# InterfaceConfiguracao.net
KiCad netlist of a schematic drawn in Altium Designer
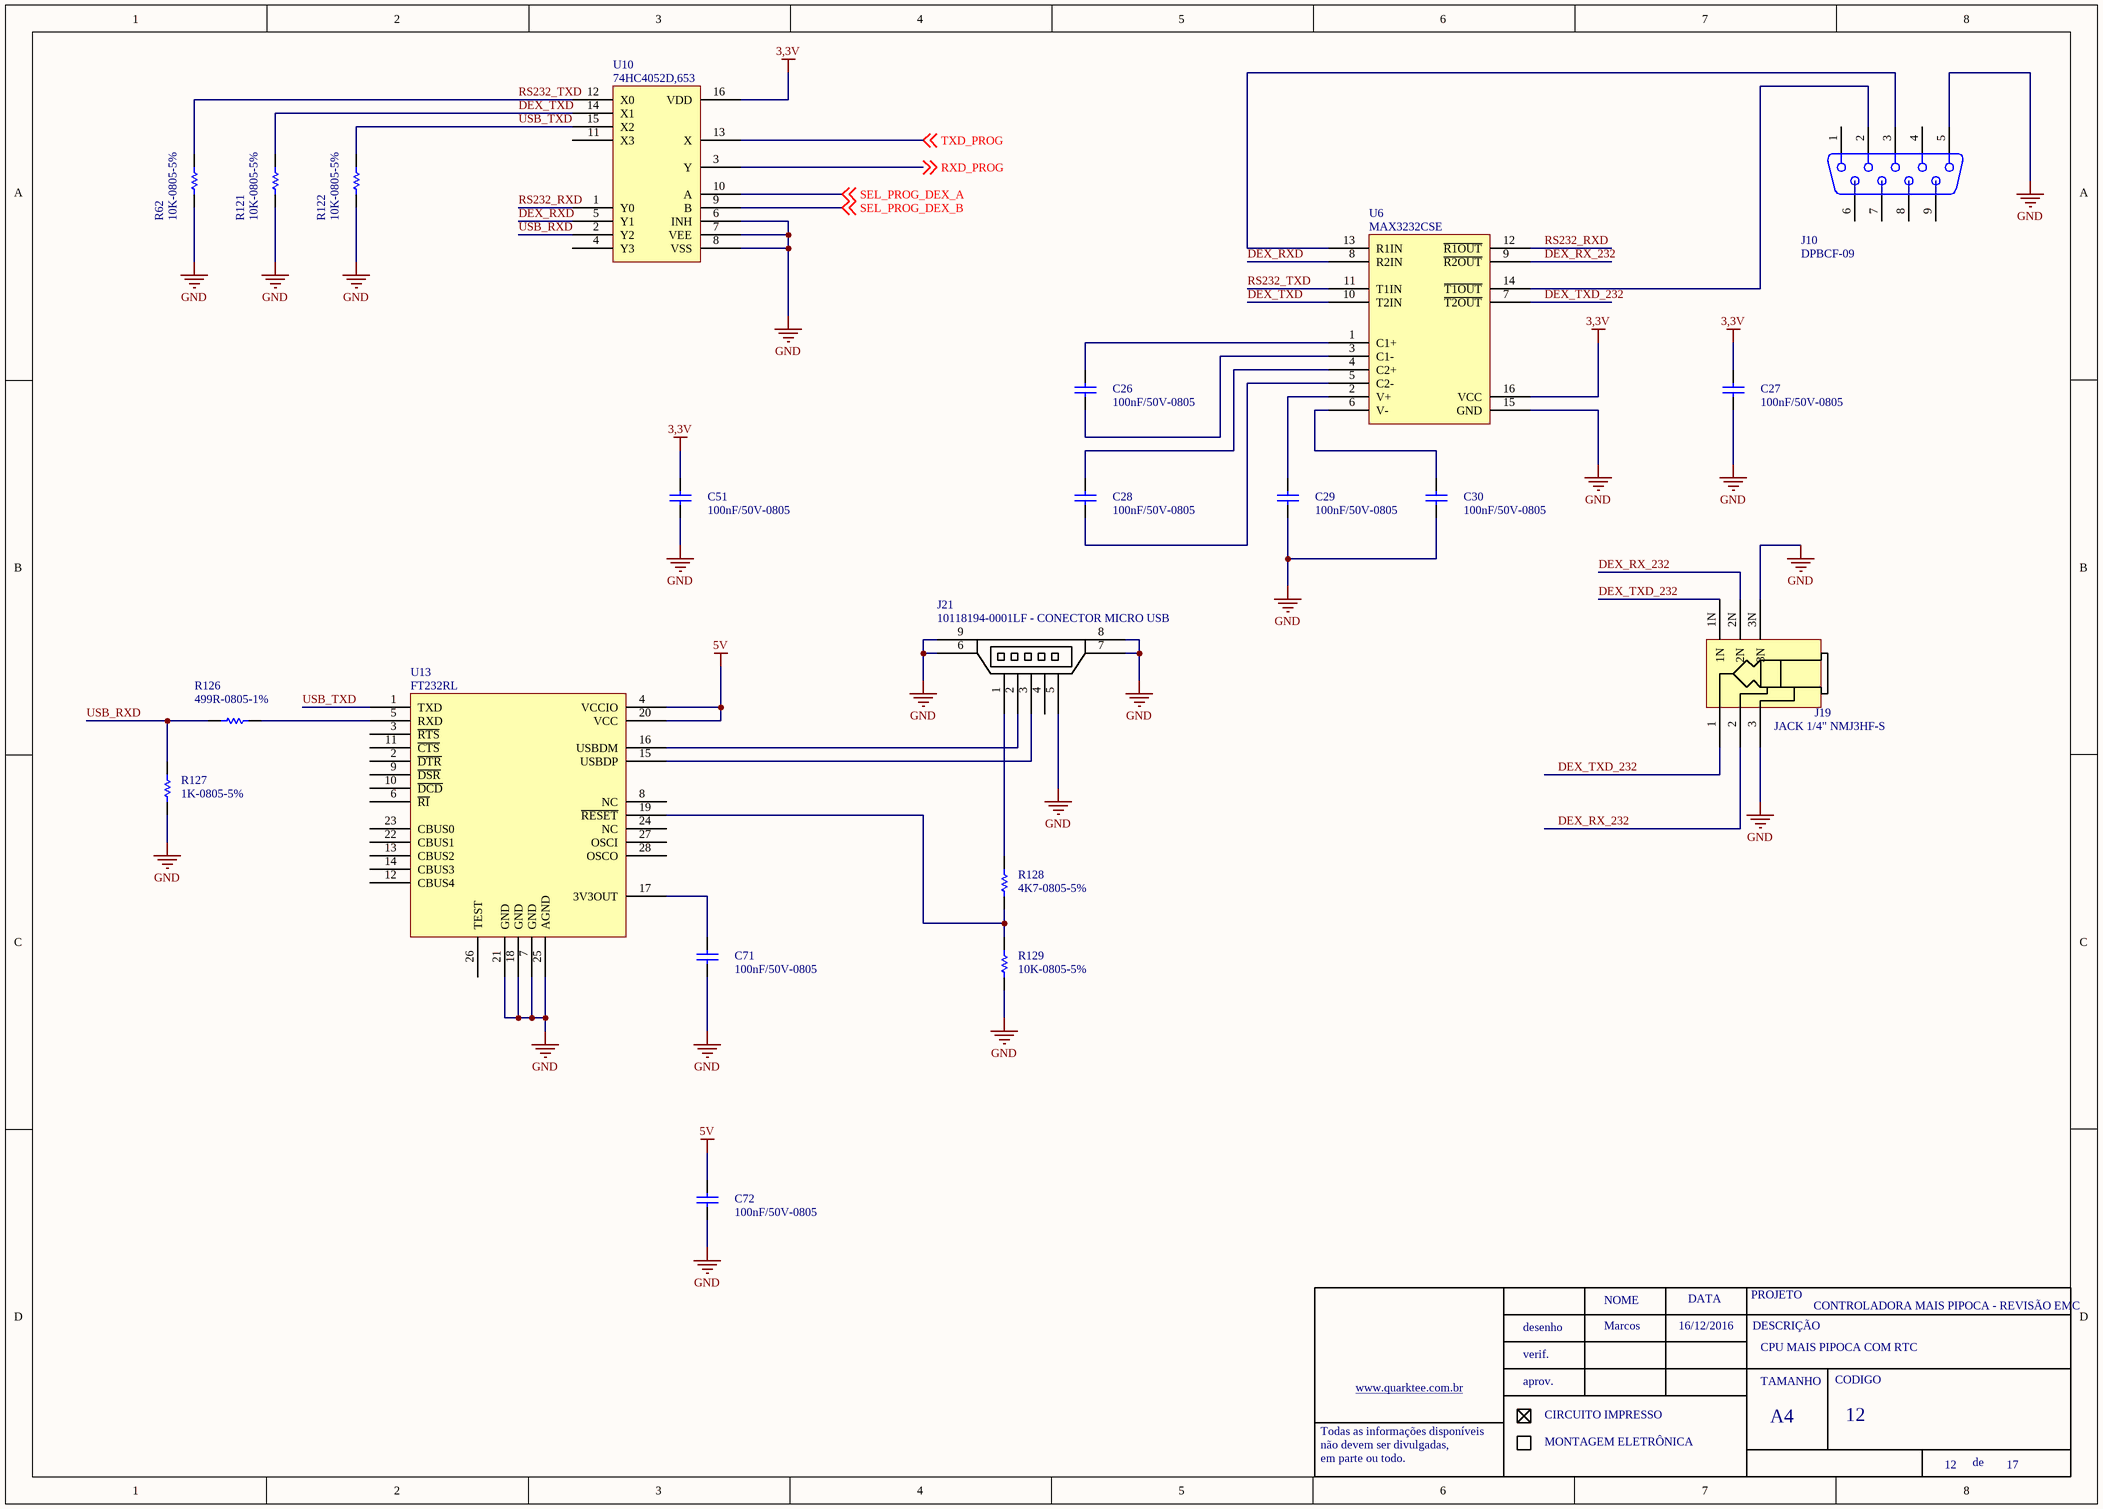
[diagram p0: InterfaceConfiguracao.SchDoc]

(export (version "E")
  (design (tool "Eeschema 10.0.6"))
  (components
    (comp (ref "C26")
      (value "100nF/50V-0805")
      (footprint "0805-REVISADO ONDA")
      (description "100nF/50-0805-NPO")
      (libsource (lib "AquinoLib") (part "100nF/50-0805-NPO"))
    )
    (comp (ref "C27")
      (value "100nF/50V-0805")
      (footprint "0805-REVISADO ONDA")
      (description "100nF/50-0805-NPO")
      (libsource (lib "AquinoLib") (part "100nF/50-0805-NPO"))
    )
    (comp (ref "C28")
      (value "100nF/50V-0805")
      (footprint "0805-REVISADO ONDA")
      (description "100nF/50-0805-NPO")
      (libsource (lib "AquinoLib") (part "100nF/50-0805-NPO"))
    )
    (comp (ref "C29")
      (value "100nF/50V-0805")
      (footprint "0805-REVISADO ONDA")
      (description "100nF/50-0805-NPO")
      (libsource (lib "AquinoLib") (part "100nF/50-0805-NPO"))
    )
    (comp (ref "C30")
      (value "100nF/50V-0805")
      (footprint "0805-REVISADO ONDA")
      (description "100nF/50-0805-NPO")
      (libsource (lib "AquinoLib") (part "100nF/50-0805-NPO"))
    )
    (comp (ref "C51")
      (value "100nF/50V-0805")
      (footprint "0805-REVISADO ONDA")
      (libsource (lib "AquinoLib") (part "100nF/50-0805-NPO"))
    )
    (comp (ref "C71")
      (value "100nF/50V-0805")
      (footprint "0805-REVISADO ONDA")
      (libsource (lib "AquinoLib") (part "100nF/50-0805-NPO"))
    )
    (comp (ref "C72")
      (value "100nF/50V-0805")
      (footprint "0805-REVISADO ONDA")
      (libsource (lib "AquinoLib") (part "100nF/50-0805-NPO"))
    )
    (comp (ref "J10")
      (value "DPBCF-09")
      (footprint "DB9-FÊMEA MONTAGEM EM PCI 180")
      (description "DBPCF-09")
      (libsource (lib "ChaveDigital3") (part "DB-9 - FÊMEA 180º MONTAGEM EM PCI"))
    )
    (comp (ref "J19")
      (value "JACK 1/4\" NMJ3HF-S")
      (description "NMJ3HF-S")
      (libsource (lib "AquinoLib") (part "NMJ3HF-S"))
    )
    (comp (ref "J21")
      (value "10118194-0001LF - CONECTOR MICRO USB")
      (libsource (lib "AquinoLib") (part "MINI_USB"))
    )
    (comp (ref "R62")
      (value "10K-0805-5%")
      (footprint "0805-REVISADO ONDA")
      (libsource (lib "AquinoLib") (part "10K-0805-5%"))
    )
    (comp (ref "R121")
      (value "10K-0805-5%")
      (footprint "0805-REVISADO ONDA")
      (libsource (lib "AquinoLib") (part "10K-0805-5%"))
    )
    (comp (ref "R122")
      (value "10K-0805-5%")
      (footprint "0805-REVISADO ONDA")
      (libsource (lib "AquinoLib") (part "10K-0805-5%"))
    )
    (comp (ref "R126")
      (value "499R-0805-1%")
      (footprint "0805-REVISADO ONDA")
      (description "1K-0805-5%")
      (libsource (lib "AquinoLib") (part "1K-0805-5%"))
    )
    (comp (ref "R127")
      (value "1K-0805-5%")
      (footprint "0805-REVISADO ONDA")
      (libsource (lib "AquinoLib") (part "1K-0805-5%"))
    )
    (comp (ref "R128")
      (value "4K7-0805-5%")
      (footprint "0805-REVISADO ONDA")
      (description "10K-0805-5%")
      (libsource (lib "AquinoLib") (part "10K-0805-5%"))
    )
    (comp (ref "R129")
      (value "10K-0805-5%")
      (footprint "0805-REVISADO ONDA")
      (libsource (lib "AquinoLib") (part "10K-0805-5%"))
    )
    (comp (ref "U6")
      (value "MAX3232CSE")
      (footprint "SOIC 16 PINOS")
      (libsource (lib "ChaveDigital3") (part "MAX3232CSE"))
    )
    (comp (ref "U10") (value "74HC4052D,653") (libsource (lib "AquinoLib") (part "CD74HC4052PWR")))
    (comp (ref "U13") (value "FT232RL") (libsource (lib "AquinoLib") (part "FT232RL")))
  )
  (nets
    (net (code "1") (name "/DEX_RXD") (class "Default")
      (node (ref "U10") (pin "5") (pinfunction "Y1_5") (pintype "passive"))
      (node (ref "U6") (pin "8") (pinfunction "R2IN_8") (pintype "passive"))
    )
    (net (code "2") (name "/DEX_RX_232") (class "Default")
      (node (ref "J19") (pin "2") (pinfunction "2_2") (pintype "passive"))
      (node (ref "J19") (pin "2N") (pinfunction "2N_2N") (pintype "passive"))
      (node (ref "U6") (pin "9") (pinfunction "~{R2OUT}_9") (pintype "passive"))
    )
    (net (code "3") (name "/DEX_TXD") (class "Default")
      (node (ref "R121") (pin "2") (pinfunction "2_2") (pintype "passive"))
      (node (ref "U10") (pin "14") (pinfunction "X1_14") (pintype "passive"))
      (node (ref "U6") (pin "10") (pinfunction "T2IN_10") (pintype "passive"))
    )
    (net (code "4") (name "/DEX_TXD_232") (class "Default")
      (node (ref "J19") (pin "1") (pinfunction "1_1") (pintype "passive"))
      (node (ref "J19") (pin "1N") (pinfunction "1N_1N") (pintype "passive"))
      (node (ref "U6") (pin "7") (pinfunction "~{T2OUT}_7") (pintype "passive"))
    )
    (net (code "5") (name "/RS232_RXD") (class "Default")
      (node (ref "U10") (pin "1") (pinfunction "Y0_1") (pintype "passive"))
      (node (ref "U6") (pin "12") (pinfunction "~{R1OUT}_12") (pintype "passive"))
    )
    (net (code "6") (name "/RS232_TXD") (class "Default")
      (node (ref "R62") (pin "2") (pinfunction "2_2") (pintype "passive"))
      (node (ref "U10") (pin "12") (pinfunction "X0_12") (pintype "passive"))
      (node (ref "U6") (pin "11") (pinfunction "T1IN_11") (pintype "passive"))
    )
    (net (code "7") (name "/USB_RXD") (class "Default")
      (node (ref "R126") (pin "1") (pinfunction "1_1") (pintype "passive"))
      (node (ref "R127") (pin "2") (pinfunction "2_2") (pintype "passive"))
      (node (ref "U10") (pin "2") (pinfunction "Y2_2") (pintype "passive"))
    )
    (net (code "8") (name "/USB_TXD") (class "Default")
      (node (ref "R122") (pin "2") (pinfunction "2_2") (pintype "passive"))
      (node (ref "U10") (pin "15") (pinfunction "X2_15") (pintype "passive"))
      (node (ref "U13") (pin "1") (pinfunction "TXD_1") (pintype "passive"))
    )
    (net (code "9") (name "3,3V") (class "Default")
      (node (ref "C27") (pin "2") (pinfunction "2_2") (pintype "passive"))
      (node (ref "C51") (pin "2") (pinfunction "2_2") (pintype "passive"))
      (node (ref "U10") (pin "16") (pinfunction "VDD_16") (pintype "passive"))
      (node (ref "U6") (pin "16") (pinfunction "VCC_16") (pintype "passive"))
    )
    (net (code "10") (name "5V") (class "Default")
      (node (ref "C72") (pin "2") (pinfunction "2_2") (pintype "passive"))
      (node (ref "U13") (pin "20") (pinfunction "VCC_20") (pintype "passive"))
      (node (ref "U13") (pin "4") (pinfunction "VCCIO_4") (pintype "passive"))
    )
    (net (code "11") (name "GND") (class "Default")
      (node (ref "C27") (pin "1") (pinfunction "1_1") (pintype "passive"))
      (node (ref "C29") (pin "1") (pinfunction "1_1") (pintype "passive"))
      (node (ref "C30") (pin "1") (pinfunction "1_1") (pintype "passive"))
      (node (ref "C51") (pin "1") (pinfunction "1_1") (pintype "passive"))
      (node (ref "C71") (pin "1") (pinfunction "1_1") (pintype "passive"))
      (node (ref "C72") (pin "1") (pinfunction "1_1") (pintype "passive"))
      (node (ref "J10") (pin "5") (pinfunction "5_5") (pintype "passive"))
      (node (ref "J19") (pin "3") (pinfunction "3_3") (pintype "passive"))
      (node (ref "J19") (pin "3N") (pinfunction "3N_3N") (pintype "passive"))
      (node (ref "J21") (pin "5") (pinfunction "5_5") (pintype "passive"))
      (node (ref "J21") (pin "6") (pinfunction "6_6") (pintype "passive"))
      (node (ref "J21") (pin "7") (pinfunction "7_7") (pintype "passive"))
      (node (ref "J21") (pin "8") (pinfunction "8_8") (pintype "passive"))
      (node (ref "J21") (pin "9") (pinfunction "9_9") (pintype "passive"))
      (node (ref "R121") (pin "1") (pinfunction "1_1") (pintype "passive"))
      (node (ref "R122") (pin "1") (pinfunction "1_1") (pintype "passive"))
      (node (ref "R127") (pin "1") (pinfunction "1_1") (pintype "passive"))
      (node (ref "R129") (pin "1") (pinfunction "1_1") (pintype "passive"))
      (node (ref "R62") (pin "1") (pinfunction "1_1") (pintype "passive"))
      (node (ref "U10") (pin "6") (pinfunction "INH_6") (pintype "passive"))
      (node (ref "U10") (pin "7") (pinfunction "VEE_7") (pintype "passive"))
      (node (ref "U10") (pin "8") (pinfunction "VSS_8") (pintype "passive"))
      (node (ref "U13") (pin "18") (pinfunction "GND_18") (pintype "passive"))
      (node (ref "U13") (pin "21") (pinfunction "GND_21") (pintype "passive"))
      (node (ref "U13") (pin "25") (pinfunction "AGND_25") (pintype "passive"))
      (node (ref "U13") (pin "7") (pinfunction "GND_7") (pintype "passive"))
      (node (ref "U6") (pin "15") (pinfunction "GND_15") (pintype "passive"))
    )
    (net (code "12") (name "Net-(J21-Pad1)") (class "Default")
      (node (ref "J21") (pin "1") (pinfunction "1_1") (pintype "passive"))
      (node (ref "R128") (pin "2") (pinfunction "2_2") (pintype "passive"))
    )
    (net (code "13") (name "Net-(U6-C1+)") (class "Default")
      (node (ref "C26") (pin "2") (pinfunction "2_2") (pintype "passive"))
      (node (ref "U6") (pin "1") (pinfunction "C1+_1") (pintype "passive"))
    )
    (net (code "14") (name "Net-(U6-C1-)") (class "Default")
      (node (ref "C26") (pin "1") (pinfunction "1_1") (pintype "passive"))
      (node (ref "U6") (pin "3") (pinfunction "C1-_3") (pintype "passive"))
    )
    (net (code "15") (name "Net-(U6-C2+)") (class "Default")
      (node (ref "C28") (pin "2") (pinfunction "2_2") (pintype "passive"))
      (node (ref "U6") (pin "4") (pinfunction "C2+_4") (pintype "passive"))
    )
    (net (code "16") (name "Net-(U6-C2-)") (class "Default")
      (node (ref "C28") (pin "1") (pinfunction "1_1") (pintype "passive"))
      (node (ref "U6") (pin "5") (pinfunction "C2-_5") (pintype "passive"))
    )
    (net (code "17") (name "Net-(U6-R1IN)") (class "Default")
      (node (ref "J10") (pin "3") (pinfunction "3_3") (pintype "passive"))
      (node (ref "U6") (pin "13") (pinfunction "R1IN_13") (pintype "passive"))
    )
    (net (code "18") (name "Net-(U6-V+)") (class "Default")
      (node (ref "C29") (pin "2") (pinfunction "2_2") (pintype "passive"))
      (node (ref "U6") (pin "2") (pinfunction "V+_2") (pintype "passive"))
    )
    (net (code "19") (name "Net-(U6-V-)") (class "Default")
      (node (ref "C30") (pin "2") (pinfunction "2_2") (pintype "passive"))
      (node (ref "U6") (pin "6") (pinfunction "V-_6") (pintype "passive"))
    )
    (net (code "20") (name "Net-(U6-~{T1OUT})") (class "Default")
      (node (ref "J10") (pin "2") (pinfunction "2_2") (pintype "passive"))
      (node (ref "U6") (pin "14") (pinfunction "~{T1OUT}_14") (pintype "passive"))
    )
    (net (code "21") (name "Net-(U13-3V3OUT)") (class "Default")
      (node (ref "C71") (pin "2") (pinfunction "2_2") (pintype "passive"))
      (node (ref "U13") (pin "17") (pinfunction "3V3OUT_17") (pintype "passive"))
    )
    (net (code "22") (name "Net-(U13-RXD)") (class "Default")
      (node (ref "R126") (pin "2") (pinfunction "2_2") (pintype "passive"))
      (node (ref "U13") (pin "5") (pinfunction "RXD_5") (pintype "passive"))
    )
    (net (code "23") (name "Net-(U13-USBDM)") (class "Default")
      (node (ref "J21") (pin "2") (pinfunction "2_2") (pintype "passive"))
      (node (ref "U13") (pin "16") (pinfunction "USBDM_16") (pintype "passive"))
    )
    (net (code "24") (name "Net-(U13-USBDP)") (class "Default")
      (node (ref "J21") (pin "3") (pinfunction "3_3") (pintype "passive"))
      (node (ref "U13") (pin "15") (pinfunction "USBDP_15") (pintype "passive"))
    )
    (net (code "25") (name "Net-(U13-~{RESET})") (class "Default")
      (node (ref "R128") (pin "1") (pinfunction "1_1") (pintype "passive"))
      (node (ref "R129") (pin "2") (pinfunction "2_2") (pintype "passive"))
      (node (ref "U13") (pin "19") (pinfunction "~{RESET}_19") (pintype "passive"))
    )
    (net (code "26") (name "RXD_PROG") (class "Default")
      (node (ref "U10") (pin "3") (pinfunction "Y_3") (pintype "passive"))
    )
    (net (code "27") (name "SEL_PROG_DEX_A") (class "Default")
      (node (ref "U10") (pin "10") (pinfunction "A_10") (pintype "passive"))
    )
    (net (code "28") (name "SEL_PROG_DEX_B") (class "Default")
      (node (ref "U10") (pin "9") (pinfunction "B_9") (pintype "passive"))
    )
    (net (code "29") (name "TXD_PROG") (class "Default")
      (node (ref "U10") (pin "13") (pinfunction "X_13") (pintype "passive"))
    )
    (net (code "30") (name "unconnected-(J10-Pad1)") (class "Default")
      (node (ref "J10") (pin "1") (pinfunction "1_1") (pintype "passive"))
    )
    (net (code "31") (name "unconnected-(J10-Pad4)") (class "Default")
      (node (ref "J10") (pin "4") (pinfunction "4_4") (pintype "passive"))
    )
    (net (code "32") (name "unconnected-(J10-Pad6)") (class "Default")
      (node (ref "J10") (pin "6") (pinfunction "6_6") (pintype "passive"))
    )
    (net (code "33") (name "unconnected-(J10-Pad7)") (class "Default")
      (node (ref "J10") (pin "7") (pinfunction "7_7") (pintype "passive"))
    )
    (net (code "34") (name "unconnected-(J10-Pad8)") (class "Default")
      (node (ref "J10") (pin "8") (pinfunction "8_8") (pintype "passive"))
    )
    (net (code "35") (name "unconnected-(J10-Pad9)") (class "Default")
      (node (ref "J10") (pin "9") (pinfunction "9_9") (pintype "passive"))
    )
    (net (code "36") (name "unconnected-(J21-Pad4)") (class "Default")
      (node (ref "J21") (pin "4") (pinfunction "4_4") (pintype "passive"))
    )
    (net (code "37") (name "unconnected-(U10-X3-Pad11)") (class "Default")
      (node (ref "U10") (pin "11") (pinfunction "X3_11") (pintype "passive"))
    )
    (net (code "38") (name "unconnected-(U10-Y3-Pad4)") (class "Default")
      (node (ref "U10") (pin "4") (pinfunction "Y3_4") (pintype "passive"))
    )
    (net (code "39") (name "unconnected-(U13-CBUS0-Pad23)") (class "Default")
      (node (ref "U13") (pin "23") (pinfunction "CBUS0_23") (pintype "passive"))
    )
    (net (code "40") (name "unconnected-(U13-CBUS1-Pad22)") (class "Default")
      (node (ref "U13") (pin "22") (pinfunction "CBUS1_22") (pintype "passive"))
    )
    (net (code "41") (name "unconnected-(U13-CBUS2-Pad13)") (class "Default")
      (node (ref "U13") (pin "13") (pinfunction "CBUS2_13") (pintype "passive"))
    )
    (net (code "42") (name "unconnected-(U13-CBUS3-Pad14)") (class "Default")
      (node (ref "U13") (pin "14") (pinfunction "CBUS3_14") (pintype "passive"))
    )
    (net (code "43") (name "unconnected-(U13-CBUS4-Pad12)") (class "Default")
      (node (ref "U13") (pin "12") (pinfunction "CBUS4_12") (pintype "passive"))
    )
    (net (code "44") (name "unconnected-(U13-NC-Pad8)") (class "Default")
      (node (ref "U13") (pin "8") (pinfunction "NC_8") (pintype "passive"))
    )
    (net (code "45") (name "unconnected-(U13-NC-Pad24)") (class "Default")
      (node (ref "U13") (pin "24") (pinfunction "NC_24") (pintype "passive"))
    )
    (net (code "46") (name "unconnected-(U13-OSCI-Pad27)") (class "Default")
      (node (ref "U13") (pin "27") (pinfunction "OSCI_27") (pintype "passive"))
    )
    (net (code "47") (name "unconnected-(U13-OSCO-Pad28)") (class "Default")
      (node (ref "U13") (pin "28") (pinfunction "OSCO_28") (pintype "passive"))
    )
    (net (code "48") (name "unconnected-(U13-TEST-Pad26)") (class "Default")
      (node (ref "U13") (pin "26") (pinfunction "TEST_26") (pintype "passive"))
    )
    (net (code "49") (name "unconnected-(U13-~{CTS}-Pad11)") (class "Default")
      (node (ref "U13") (pin "11") (pinfunction "~{CTS}_11") (pintype "passive"))
    )
    (net (code "50") (name "unconnected-(U13-~{DCD}-Pad10)") (class "Default")
      (node (ref "U13") (pin "10") (pinfunction "~{DCD}_10") (pintype "passive"))
    )
    (net (code "51") (name "unconnected-(U13-~{DSR}-Pad9)") (class "Default")
      (node (ref "U13") (pin "9") (pinfunction "~{DSR}_9") (pintype "passive"))
    )
    (net (code "52") (name "unconnected-(U13-~{DTR}-Pad2)") (class "Default")
      (node (ref "U13") (pin "2") (pinfunction "~{DTR}_2") (pintype "passive"))
    )
    (net (code "53") (name "unconnected-(U13-~{RI}-Pad6)") (class "Default")
      (node (ref "U13") (pin "6") (pinfunction "~{RI}_6") (pintype "passive"))
    )
    (net (code "54") (name "unconnected-(U13-~{RTS}-Pad3)") (class "Default")
      (node (ref "U13") (pin "3") (pinfunction "~{RTS}_3") (pintype "passive"))
    )
  )
)
